# StatusLEDs.net
KiCad netlist of a schematic drawn in Altium Designer
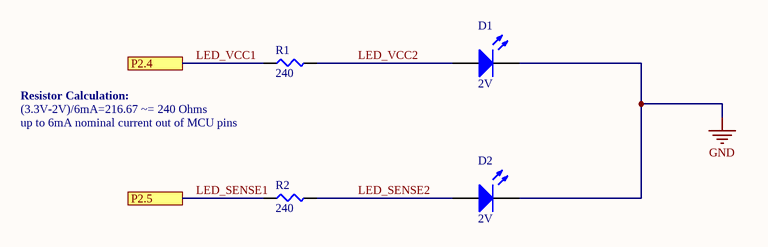
[diagram p0: StatusLEDs.SchDoc]

(export (version "E")
  (design (tool "Eeschema 10.0.6"))
  (components
    (comp (ref "D1")
      (value "2V")
      (footprint "0805_A")
      (description "SMD mono-color Chip LED, WL-SMCW, Bright Green, 150080VS75000")
      (fields (field (name "PARTNUMBER") "150080VS75000") (field (name "MANUFACTURER") "Wuerth Elektronik"))
      (libsource (lib "Altium Content Vault") (part "WE-LED_K1A2-2"))
    )
    (comp (ref "D2")
      (value "2V")
      (footprint "0805_A")
      (description "SMD mono-color Chip LED, WL-SMCW, Bright Green, 150080VS75000")
      (fields (field (name "PARTNUMBER") "150080VS75000") (field (name "MANUFACTURER") "Wuerth Elektronik"))
      (libsource (lib "Altium Content Vault") (part "WE-LED_K1A2-2"))
    )
    (comp (ref "R1")
      (value "240")
      (footprint "SMD-0805-RES")
      (description "RES SMD 240 OHM 1% 1/8W 0805")
      (fields (field (name "PART NUMBER") "ERJ-6ENF2400V") (field (name "DIGI-KEY PART NUMBER") "P240CCT-ND"))
      (libsource (lib "Panasonic_resistor_0805") (part "ERJ-6ENF2400V"))
    )
    (comp (ref "R2")
      (value "240")
      (footprint "SMD-0805-RES")
      (description "RES SMD 240 OHM 1% 1/8W 0805")
      (fields (field (name "PART NUMBER") "ERJ-6ENF2400V") (field (name "DIGI-KEY PART NUMBER") "P240CCT-ND"))
      (libsource (lib "Panasonic_resistor_0805") (part "ERJ-6ENF2400V"))
    )
  )
  (nets
    (net (code "1") (name "/LED_SENSE1") (class "Default")
      (node (ref "R2") (pin "1") (pinfunction "1_1") (pintype "passive"))
    )
    (net (code "2") (name "/LED_SENSE2") (class "Default")
      (node (ref "D2") (pin "2") (pinfunction "A_2") (pintype "passive"))
      (node (ref "R2") (pin "2") (pinfunction "2_2") (pintype "passive"))
    )
    (net (code "3") (name "/LED_VCC1") (class "Default")
      (node (ref "R1") (pin "1") (pinfunction "1_1") (pintype "passive"))
    )
    (net (code "4") (name "/LED_VCC2") (class "Default")
      (node (ref "D1") (pin "2") (pinfunction "A_2") (pintype "passive"))
      (node (ref "R1") (pin "2") (pinfunction "2_2") (pintype "passive"))
    )
    (net (code "5") (name "GND") (class "Default")
      (node (ref "D1") (pin "1") (pinfunction "K_1") (pintype "passive"))
      (node (ref "D2") (pin "1") (pinfunction "K_1") (pintype "passive"))
    )
  )
)
